# PSU.net
KiCad netlist of a schematic drawn in Altium Designer
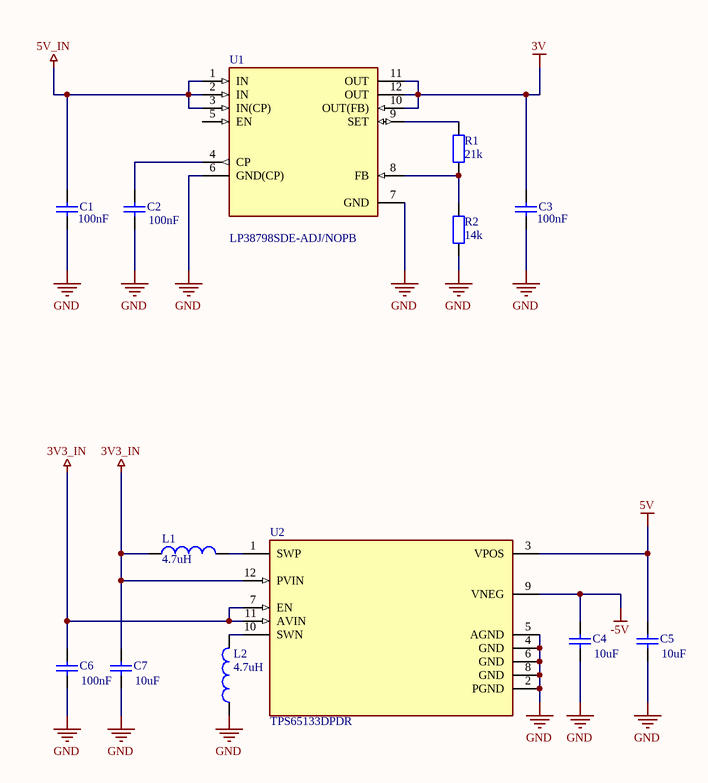
[diagram p0: PSU.SchDoc]

(export (version "E")
  (design (tool "Eeschema 10.0.6"))
  (components
    (comp (ref "C1")
      (value "100nF")
      (footprint "C1206")
      (description "Capacitor (Semiconductor SIM Model)")
      (fields (field (name "Comment") "Cap Semi") (field (name "PUBLISHER") "Altium Limited"))
      (libsource (lib "Miscellaneous Devices") (part "Cap Semi"))
    )
    (comp (ref "C2")
      (value "100nF")
      (footprint "C1206")
      (description "Capacitor (Semiconductor SIM Model)")
      (fields (field (name "Comment") "Cap Semi") (field (name "PUBLISHER") "Altium Limited"))
      (libsource (lib "Miscellaneous Devices") (part "Cap Semi"))
    )
    (comp (ref "C3")
      (value "100nF")
      (footprint "C1206")
      (description "Capacitor (Semiconductor SIM Model)")
      (fields (field (name "Comment") "Cap Semi") (field (name "PUBLISHER") "Altium Limited"))
      (libsource (lib "Miscellaneous Devices") (part "Cap Semi"))
    )
    (comp (ref "C4")
      (value "10uF")
      (footprint "C1206")
      (description "Capacitor (Semiconductor SIM Model)")
      (fields (field (name "Comment") "Cap Semi") (field (name "PUBLISHER") "Altium Limited"))
      (libsource (lib "Miscellaneous Devices") (part "Cap Semi"))
    )
    (comp (ref "C5")
      (value "10uF")
      (footprint "C1206")
      (description "Capacitor (Semiconductor SIM Model)")
      (fields (field (name "Comment") "Cap Semi") (field (name "PUBLISHER") "Altium Limited"))
      (libsource (lib "Miscellaneous Devices") (part "Cap Semi"))
    )
    (comp (ref "C6")
      (value "100nF")
      (footprint "C1206")
      (description "Capacitor (Semiconductor SIM Model)")
      (fields (field (name "Comment") "Cap Semi") (field (name "PUBLISHER") "Altium Limited"))
      (libsource (lib "Miscellaneous Devices") (part "Cap Semi"))
    )
    (comp (ref "C7")
      (value "10uF")
      (footprint "C1206")
      (description "Capacitor (Semiconductor SIM Model)")
      (fields (field (name "Comment") "Cap Semi") (field (name "PUBLISHER") "Altium Limited"))
      (libsource (lib "Miscellaneous Devices") (part "Cap Semi"))
    )
    (comp (ref "L1")
      (value "4.7uH")
      (footprint "0402-A")
      (description "Inductor")
      (fields (field (name "PUBLISHER") "Altium Limited"))
      (libsource (lib "Miscellaneous Devices") (part "Inductor"))
    )
    (comp (ref "L2")
      (value "4.7uH")
      (footprint "0402-A")
      (description "Inductor")
      (fields (field (name "PUBLISHER") "Altium Limited"))
      (libsource (lib "Miscellaneous Devices") (part "Inductor"))
    )
    (comp (ref "R1")
      (value "21k")
      (footprint "AXIAL-0.4")
      (description "Resistor")
      (fields (field (name "Comment") "Res2") (field (name "PUBLISHER") "Altium Limited"))
      (libsource (lib "Miscellaneous Devices") (part "Res2"))
    )
    (comp (ref "R2")
      (value "14k")
      (footprint "AXIAL-0.4")
      (description "Resistor")
      (fields (field (name "Comment") "Res2") (field (name "PUBLISHER") "Altium Limited"))
      (libsource (lib "Miscellaneous Devices") (part "Res2"))
    )
    (comp (ref "U1")
      (value "LP38798SDE-ADJ-NOPB")
      (footprint "Texas_Instruments_DNT0012B_0")
      (description "IC REG LIN POS ADJ 800MA 12WSON")
      (fields
        (field (name "PART NUMBER") "LP38798SDE-ADJ/NOPB")
        (field (name "DIGIKEY PART NUMBER") "296-36225-1-ND")
      )
      (libsource (lib "EEConcierge") (part "LP38798SDE-ADJ-NOPB"))
    )
    (comp (ref "U2")
      (value "TPS65133DPDR")
      (footprint "FP-DPD0012A-MFG")
      (description "IC REG AMOLED DISPL 2OUT 12WSON")
      (libsource (lib "Altium Content Vault") (part "cb0e1e7d26f86b63177112bdd55f499"))
    )
  )
  (nets
    (net (code "1") (name "-5V") (class "Default")
      (node (ref "C4") (pin "2") (pinfunction "2_2") (pintype "passive"))
      (node (ref "U2") (pin "9") (pinfunction "VNEG_9") (pintype "power_in"))
    )
    (net (code "2") (name "3V") (class "Default")
      (node (ref "C3") (pin "2") (pinfunction "2_2") (pintype "passive"))
      (node (ref "U1") (pin "10") (pinfunction "OUT(FB)_10") (pintype "input"))
      (node (ref "U1") (pin "11") (pinfunction "OUT_11") (pintype "power_in"))
      (node (ref "U1") (pin "12") (pinfunction "OUT_12") (pintype "power_in"))
    )
    (net (code "3") (name "3V3_IN") (class "Default")
      (node (ref "C6") (pin "2") (pinfunction "2_2") (pintype "passive"))
      (node (ref "C7") (pin "2") (pinfunction "2_2") (pintype "passive"))
      (node (ref "L1") (pin "1") (pinfunction "1_1") (pintype "passive"))
      (node (ref "U2") (pin "11") (pinfunction "AVIN_11") (pintype "input"))
      (node (ref "U2") (pin "12") (pinfunction "PVIN_12") (pintype "input"))
      (node (ref "U2") (pin "7") (pinfunction "EN_7") (pintype "input"))
    )
    (net (code "4") (name "5V") (class "Default")
      (node (ref "C5") (pin "2") (pinfunction "2_2") (pintype "passive"))
      (node (ref "U2") (pin "3") (pinfunction "VPOS_3") (pintype "power_in"))
    )
    (net (code "5") (name "5V_IN") (class "Default")
      (node (ref "C1") (pin "2") (pinfunction "2_2") (pintype "passive"))
      (node (ref "U1") (pin "1") (pinfunction "IN_1") (pintype "input"))
      (node (ref "U1") (pin "2") (pinfunction "IN_2") (pintype "input"))
      (node (ref "U1") (pin "3") (pinfunction "IN(CP)_3") (pintype "input"))
    )
    (net (code "6") (name "GND") (class "Default")
      (node (ref "C1") (pin "1") (pinfunction "1_1") (pintype "passive"))
      (node (ref "C2") (pin "1") (pinfunction "1_1") (pintype "passive"))
      (node (ref "C3") (pin "1") (pinfunction "1_1") (pintype "passive"))
      (node (ref "C4") (pin "1") (pinfunction "1_1") (pintype "passive"))
      (node (ref "C5") (pin "1") (pinfunction "1_1") (pintype "passive"))
      (node (ref "C6") (pin "1") (pinfunction "1_1") (pintype "passive"))
      (node (ref "C7") (pin "1") (pinfunction "1_1") (pintype "passive"))
      (node (ref "L2") (pin "1") (pinfunction "1_1") (pintype "passive"))
      (node (ref "R2") (pin "1") (pinfunction "1_1") (pintype "passive"))
      (node (ref "U1") (pin "6") (pinfunction "GND(CP)_6") (pintype "power_in"))
      (node (ref "U1") (pin "7") (pinfunction "GND_7") (pintype "power_in"))
      (node (ref "U2") (pin "2") (pinfunction "PGND_2") (pintype "power_in"))
      (node (ref "U2") (pin "4") (pinfunction "GND_4") (pintype "power_in"))
      (node (ref "U2") (pin "5") (pinfunction "AGND_5") (pintype "power_in"))
      (node (ref "U2") (pin "6") (pinfunction "GND_6") (pintype "power_in"))
      (node (ref "U2") (pin "8") (pinfunction "GND_8") (pintype "power_in"))
    )
    (net (code "7") (name "Net-(U1-CP)") (class "Default")
      (node (ref "C2") (pin "2") (pinfunction "2_2") (pintype "passive"))
      (node (ref "U1") (pin "4") (pinfunction "CP_4") (pintype "output"))
    )
    (net (code "8") (name "Net-(U1-FB)") (class "Default")
      (node (ref "R1") (pin "1") (pinfunction "1_1") (pintype "passive"))
      (node (ref "R2") (pin "2") (pinfunction "2_2") (pintype "passive"))
      (node (ref "U1") (pin "8") (pinfunction "FB_8") (pintype "input"))
    )
    (net (code "9") (name "Net-(U1-SET)") (class "Default")
      (node (ref "R1") (pin "2") (pinfunction "2_2") (pintype "passive"))
      (node (ref "U1") (pin "9") (pinfunction "SET_9") (pintype "bidirectional"))
    )
    (net (code "10") (name "Net-(U2-SWN)") (class "Default")
      (node (ref "L2") (pin "2") (pinfunction "2_2") (pintype "passive"))
      (node (ref "U2") (pin "10") (pinfunction "SWN_10") (pintype "power_in"))
    )
    (net (code "11") (name "Net-(U2-SWP)") (class "Default")
      (node (ref "L1") (pin "2") (pinfunction "2_2") (pintype "passive"))
      (node (ref "U2") (pin "1") (pinfunction "SWP_1") (pintype "power_in"))
    )
    (net (code "12") (name "unconnected-(U1-EN-Pad5)") (class "Default")
      (node (ref "U1") (pin "5") (pinfunction "EN_5") (pintype "input"))
    )
  )
)
